# JTAG_Interface.net
KiCad netlist of a schematic drawn in Altium Designer
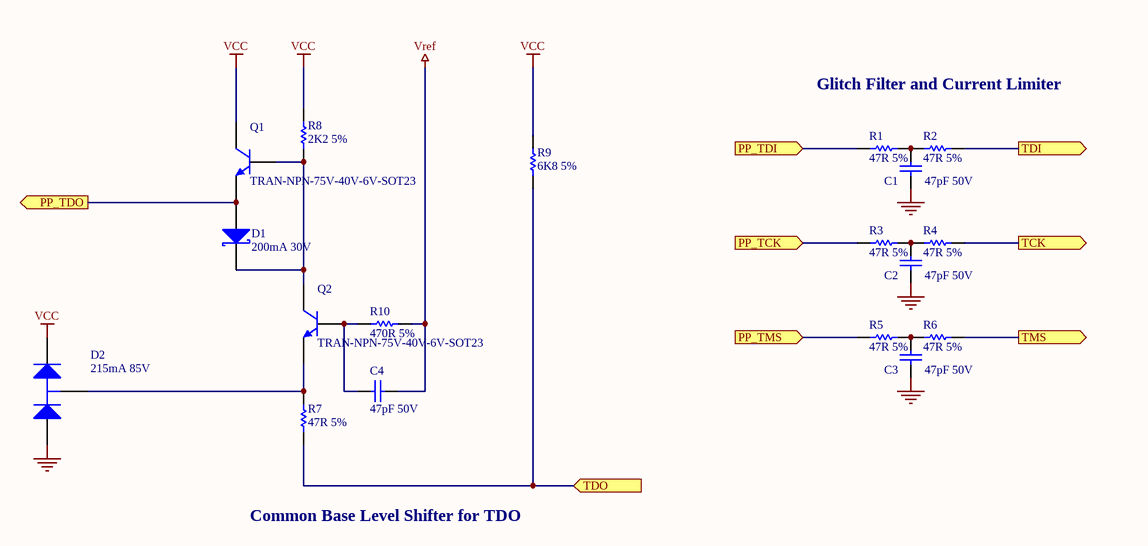
[diagram p0: JTAG Interface.SchDoc]

(export (version "E")
  (design (tool "Eeschema 10.0.6"))
  (components
    (comp (ref "C1")
      (value "47pF 50V")
      (footprint "CAPC2012")
      (description "Capacitor")
      (libsource (lib "Altium Design Library") (part "CAP-NP"))
    )
    (comp (ref "C2")
      (value "47pF 50V")
      (footprint "CAPC2012")
      (description "Capacitor")
      (libsource (lib "Altium Design Library") (part "CAP-NP"))
    )
    (comp (ref "C3")
      (value "47pF 50V")
      (footprint "CAPC2012")
      (description "Capacitor")
      (libsource (lib "Altium Design Library") (part "CAP-NP"))
    )
    (comp (ref "C4")
      (value "47pF 50V")
      (footprint "CAPC2012")
      (description "Capacitor")
      (libsource (lib "Altium Design Library") (part "CAP-NP"))
    )
    (comp (ref "D1")
      (value "200mA 30V")
      (footprint "SOT95P230-3")
      (description "Schottky Barrier Single Diode")
      (libsource (lib "Altium Design Library") (part "DIO-SCHOTTKY-1S-SOT23"))
    )
    (comp (ref "D2")
      (value "215mA 85V")
      (footprint "SOT95P230-3")
      (description "Silicon Switching Diode Array for High-Speed Switching")
      (libsource (lib "Altium Design Library") (part "DIO-2S"))
    )
    (comp (ref "Q1")
      (value "TRAN-NPN-75V-40V-6V-SOT23")
      (footprint "SOT95P230-3")
      (description "General Purpose Transistor NPN Silicon")
      (libsource (lib "Altium Design Library") (part "TRA-NPN"))
    )
    (comp (ref "Q2")
      (value "TRAN-NPN-75V-40V-6V-SOT23")
      (footprint "SOT95P230-3")
      (description "General Purpose Transistor NPN Silicon")
      (libsource (lib "Altium Design Library") (part "TRA-NPN"))
    )
    (comp (ref "R1")
      (value "47R 5%")
      (footprint "RESC2012")
      (description "Resistor")
      (libsource (lib "Altium Design Library") (part "RES"))
    )
    (comp (ref "R2")
      (value "47R 5%")
      (footprint "RESC2012")
      (description "Resistor")
      (libsource (lib "Altium Design Library") (part "RES"))
    )
    (comp (ref "R3")
      (value "47R 5%")
      (footprint "RESC2012")
      (description "Resistor")
      (libsource (lib "Altium Design Library") (part "RES"))
    )
    (comp (ref "R4")
      (value "47R 5%")
      (footprint "RESC2012")
      (description "Resistor")
      (libsource (lib "Altium Design Library") (part "RES"))
    )
    (comp (ref "R5")
      (value "47R 5%")
      (footprint "RESC2012")
      (description "Resistor")
      (libsource (lib "Altium Design Library") (part "RES"))
    )
    (comp (ref "R6")
      (value "47R 5%")
      (footprint "RESC2012")
      (description "Resistor")
      (libsource (lib "Altium Design Library") (part "RES"))
    )
    (comp (ref "R7")
      (value "47R 5%")
      (footprint "RESC2012")
      (description "Resistor")
      (libsource (lib "Altium Design Library") (part "RES"))
    )
    (comp (ref "R8")
      (value "2K2 5%")
      (footprint "RESC2012")
      (description "Resistor")
      (libsource (lib "Altium Design Library") (part "RES"))
    )
    (comp (ref "R9")
      (value "6K8 5%")
      (footprint "RESC2012")
      (description "Resistor")
      (libsource (lib "Altium Design Library") (part "RES"))
    )
    (comp (ref "R10")
      (value "470R 5%")
      (footprint "RESC2012")
      (description "Resistor")
      (libsource (lib "Altium Design Library") (part "RES"))
    )
  )
  (nets
    (net (code "1") (name "/PP_TCK") (class "Default")
      (node (ref "R3") (pin "1") (pinfunction "1_1") (pintype "passive"))
    )
    (net (code "2") (name "/PP_TDI") (class "Default")
      (node (ref "R1") (pin "1") (pinfunction "1_1") (pintype "passive"))
    )
    (net (code "3") (name "/PP_TDO") (class "Default")
      (node (ref "D1") (pin "1") (pinfunction "A_1") (pintype "passive"))
      (node (ref "Q1") (pin "2") (pinfunction "E_2") (pintype "passive"))
    )
    (net (code "4") (name "/PP_TMS") (class "Default")
      (node (ref "R5") (pin "1") (pinfunction "1_1") (pintype "passive"))
    )
    (net (code "5") (name "/TCK") (class "Default")
      (node (ref "R4") (pin "2") (pinfunction "2_2") (pintype "passive"))
    )
    (net (code "6") (name "/TDI") (class "Default")
      (node (ref "R2") (pin "2") (pinfunction "2_2") (pintype "passive"))
    )
    (net (code "7") (name "/TDO") (class "Default")
      (node (ref "R7") (pin "1") (pinfunction "1_1") (pintype "passive"))
      (node (ref "R9") (pin "1") (pinfunction "1_1") (pintype "passive"))
    )
    (net (code "8") (name "/TMS") (class "Default")
      (node (ref "R6") (pin "2") (pinfunction "2_2") (pintype "passive"))
    )
    (net (code "9") (name "GND") (class "Default")
      (node (ref "C1") (pin "2") (pinfunction "2_2") (pintype "passive"))
      (node (ref "C2") (pin "2") (pinfunction "2_2") (pintype "passive"))
      (node (ref "C3") (pin "2") (pinfunction "2_2") (pintype "passive"))
      (node (ref "D2") (pin "1") (pinfunction "A_1") (pintype "passive"))
    )
    (net (code "10") (name "Net-(C1-Pad1)") (class "Default")
      (node (ref "C1") (pin "1") (pinfunction "1_1") (pintype "passive"))
      (node (ref "R1") (pin "2") (pinfunction "2_2") (pintype "passive"))
      (node (ref "R2") (pin "1") (pinfunction "1_1") (pintype "passive"))
    )
    (net (code "11") (name "Net-(C2-Pad1)") (class "Default")
      (node (ref "C2") (pin "1") (pinfunction "1_1") (pintype "passive"))
      (node (ref "R3") (pin "2") (pinfunction "2_2") (pintype "passive"))
      (node (ref "R4") (pin "1") (pinfunction "1_1") (pintype "passive"))
    )
    (net (code "12") (name "Net-(C3-Pad1)") (class "Default")
      (node (ref "C3") (pin "1") (pinfunction "1_1") (pintype "passive"))
      (node (ref "R5") (pin "2") (pinfunction "2_2") (pintype "passive"))
      (node (ref "R6") (pin "1") (pinfunction "1_1") (pintype "passive"))
    )
    (net (code "13") (name "Net-(D1-k)") (class "Default")
      (node (ref "D1") (pin "3") (pinfunction "k_3") (pintype "passive"))
      (node (ref "Q1") (pin "1") (pinfunction "B_1") (pintype "passive"))
      (node (ref "Q2") (pin "3") (pinfunction "C_3") (pintype "passive"))
      (node (ref "R8") (pin "1") (pinfunction "1_1") (pintype "passive"))
    )
    (net (code "14") (name "Net-(D2-C)") (class "Default")
      (node (ref "D2") (pin "3") (pinfunction "C_3") (pintype "passive"))
      (node (ref "Q2") (pin "2") (pinfunction "E_2") (pintype "passive"))
      (node (ref "R7") (pin "2") (pinfunction "2_2") (pintype "passive"))
    )
    (net (code "15") (name "Net-(Q2-B)") (class "Default")
      (node (ref "C4") (pin "1") (pinfunction "1_1") (pintype "passive"))
      (node (ref "Q2") (pin "1") (pinfunction "B_1") (pintype "passive"))
      (node (ref "R10") (pin "2") (pinfunction "2_2") (pintype "passive"))
    )
    (net (code "16") (name "VCC") (class "Default")
      (node (ref "D2") (pin "2") (pinfunction "K_2") (pintype "passive"))
      (node (ref "Q1") (pin "3") (pinfunction "C_3") (pintype "passive"))
      (node (ref "R8") (pin "2") (pinfunction "2_2") (pintype "passive"))
      (node (ref "R9") (pin "2") (pinfunction "2_2") (pintype "passive"))
    )
    (net (code "17") (name "Vref") (class "Default")
      (node (ref "C4") (pin "2") (pinfunction "2_2") (pintype "passive"))
      (node (ref "R10") (pin "1") (pinfunction "1_1") (pintype "passive"))
    )
    (net (code "18") (name "unconnected-(D1-Pad2)") (class "Default")
      (node (ref "D1") (pin "2") (pintype "passive"))
    )
  )
)
